# FMU_FMU_REV_2A.net
KiCad netlist of a schematic drawn in Altium Designer
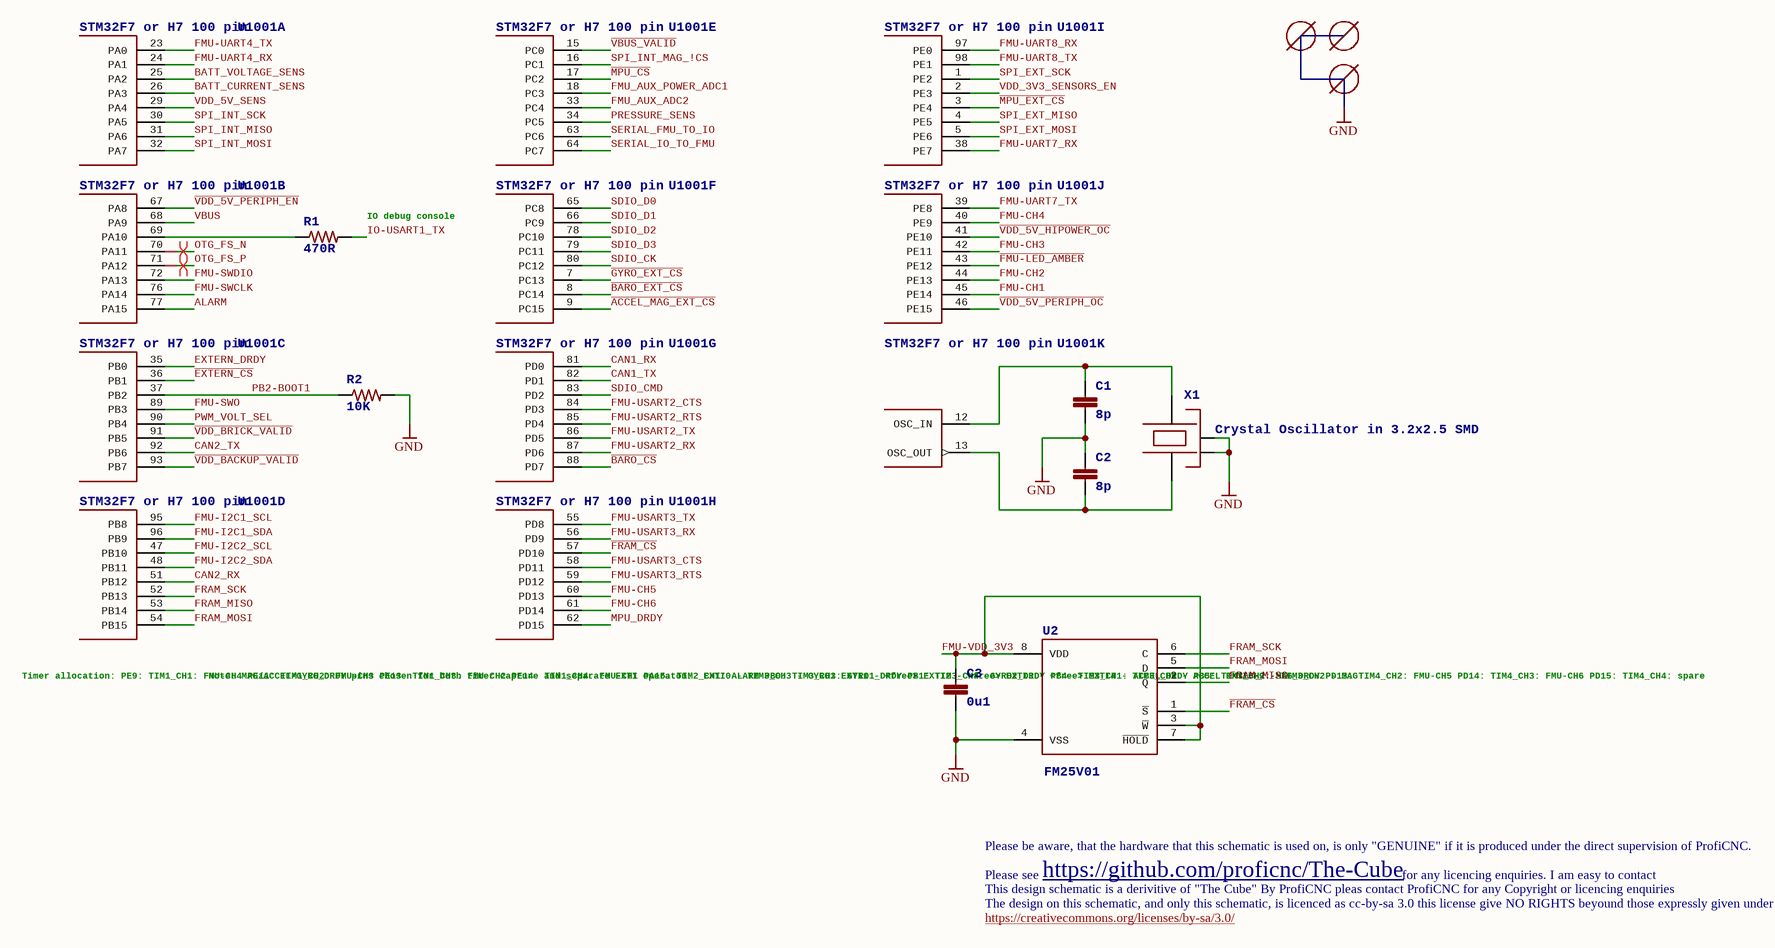
[diagram p0: FMU_FMU_REV_2A.SchDoc]

(export (version "E")
  (design (tool "Eeschema 10.0.6"))
  (components
    (comp (ref "C1")
      (value "8p")
      (footprint "0402-CAP")
      (description "CAP CER 8PF 50V C0G 0402")
      (libsource (lib "pixhawk2") (part "CAP0402"))
    )
    (comp (ref "C2")
      (value "8p")
      (footprint "0402-CAP")
      (description "CAP CER 8PF 50V C0G 0402")
      (libsource (lib "pixhawk2") (part "CAP0402"))
    )
    (comp (ref "C3")
      (value "0u1")
      (footprint "0402-CAP")
      (description "CAP CER 0.1UF 16V Y5V 0402")
      (libsource (lib "pixhawk2") (part "CAP0402"))
    )
    (comp (ref "M1")
      (value "MOUNT-HOLE1.8MM")
      (footprint "MOUNT-HOLE1.8")
      (libsource (lib "pixhawk2") (part "MOUNT-HOLE1.8MM"))
    )
    (comp (ref "M2")
      (value "MOUNT-HOLE1.8MM")
      (footprint "MOUNT-HOLE1.8")
      (libsource (lib "pixhawk2") (part "MOUNT-HOLE1.8MM"))
    )
    (comp (ref "M3")
      (value "MOUNT-HOLE1.8MM")
      (footprint "MOUNT-HOLE1.8")
      (libsource (lib "pixhawk2") (part "MOUNT-HOLE1.8MM"))
    )
    (comp (ref "R1")
      (value "470R")
      (footprint "0402-RES")
      (description "RES 470 OHM 1/16W 1% 0402 SMD")
      (libsource (lib "pixhawk2") (part "RESISTOR0402-RES"))
    )
    (comp (ref "R2")
      (value "10K")
      (footprint "0402-RES")
      (description "RES 10K OHM 1/16W 1% 0402 SMD")
      (libsource (lib "pixhawk2") (part "RESISTOR0402-RES"))
    )
    (comp (ref "U2")
      (value "FM25V01")
      (footprint "SO08")
      (description "IC FRAM 128KBIT 40MHZ 8SOIC")
      (libsource (lib "pixhawk2") (part "FM25V01"))
    )
    (comp (ref "U1001")
      (value "STM32F7 or H7 100 pin")
      (footprint "TQFP100")
      (description "REV 3 Silicon or later IC MCU ARM 2MB FLASH 100LQFP")
      (libsource (lib "pixhawk2") (part "STM32F4X7VX"))
    )
    (comp (ref "X1")
      (value "Crystal Oscillator in 3.2x2.5 SMD")
      (footprint "OSCILLATOR-3.2X2.5")
      (description "CRYSTAL 24MHZ 8PF SMD")
      (libsource (lib "pixhawk2") (part "OSCILLATOR-3.2X2.5"))
    )
  )
  (nets
    (net (code "1") (name "/ALARM") (class "Default")
      (node (ref "U1001") (pin "77") (pinfunction "PA15_77") (pintype "passive"))
    )
    (net (code "2") (name "/BATT_CURRENT_SENS") (class "Default")
      (node (ref "U1001") (pin "26") (pinfunction "PA3_26") (pintype "passive"))
    )
    (net (code "3") (name "/BATT_VOLTAGE_SENS") (class "Default")
      (node (ref "U1001") (pin "25") (pinfunction "PA2_25") (pintype "passive"))
    )
    (net (code "4") (name "/CAN1_RX") (class "Default")
      (node (ref "U1001") (pin "81") (pinfunction "PD0_81") (pintype "passive"))
    )
    (net (code "5") (name "/CAN1_TX") (class "Default")
      (node (ref "U1001") (pin "82") (pinfunction "PD1_82") (pintype "passive"))
    )
    (net (code "6") (name "/CAN2_RX") (class "Default")
      (node (ref "U1001") (pin "51") (pinfunction "PB12_51") (pintype "passive"))
    )
    (net (code "7") (name "/CAN2_TX") (class "Default")
      (node (ref "U1001") (pin "92") (pinfunction "PB6_92") (pintype "passive"))
    )
    (net (code "8") (name "/EXTERN_DRDY") (class "Default")
      (node (ref "U1001") (pin "35") (pinfunction "PB0_35") (pintype "passive"))
    )
    (net (code "9") (name "/FMU-CH1") (class "Default")
      (node (ref "U1001") (pin "45") (pinfunction "PE14_45") (pintype "passive"))
    )
    (net (code "10") (name "/FMU-CH2") (class "Default")
      (node (ref "U1001") (pin "44") (pinfunction "PE13_44") (pintype "passive"))
    )
    (net (code "11") (name "/FMU-CH3") (class "Default")
      (node (ref "U1001") (pin "42") (pinfunction "PE11_42") (pintype "passive"))
    )
    (net (code "12") (name "/FMU-CH4") (class "Default")
      (node (ref "U1001") (pin "40") (pinfunction "PE9_40") (pintype "passive"))
    )
    (net (code "13") (name "/FMU-CH5") (class "Default")
      (node (ref "U1001") (pin "60") (pinfunction "PD13_60") (pintype "passive"))
    )
    (net (code "14") (name "/FMU-CH6") (class "Default")
      (node (ref "U1001") (pin "61") (pinfunction "PD14_61") (pintype "passive"))
    )
    (net (code "15") (name "/FMU-I2C1_SCL") (class "Default")
      (node (ref "U1001") (pin "95") (pinfunction "PB8_95") (pintype "passive"))
    )
    (net (code "16") (name "/FMU-I2C1_SDA") (class "Default")
      (node (ref "U1001") (pin "96") (pinfunction "PB9_96") (pintype "passive"))
    )
    (net (code "17") (name "/FMU-I2C2_SCL") (class "Default")
      (node (ref "U1001") (pin "47") (pinfunction "PB10_47") (pintype "passive"))
    )
    (net (code "18") (name "/FMU-I2C2_SDA") (class "Default")
      (node (ref "U1001") (pin "48") (pinfunction "PB11_48") (pintype "passive"))
    )
    (net (code "19") (name "/FMU-SWCLK") (class "Default")
      (node (ref "U1001") (pin "76") (pinfunction "PA14_76") (pintype "passive"))
    )
    (net (code "20") (name "/FMU-SWDIO") (class "Default")
      (node (ref "U1001") (pin "72") (pinfunction "PA13_72") (pintype "passive"))
    )
    (net (code "21") (name "/FMU-SWO") (class "Default")
      (node (ref "U1001") (pin "89") (pinfunction "PB3_89") (pintype "passive"))
    )
    (net (code "22") (name "/FMU-UART4_RX") (class "Default")
      (node (ref "U1001") (pin "24") (pinfunction "PA1_24") (pintype "passive"))
    )
    (net (code "23") (name "/FMU-UART4_TX") (class "Default")
      (node (ref "U1001") (pin "23") (pinfunction "PA0_23") (pintype "passive"))
    )
    (net (code "24") (name "/FMU-UART7_RX") (class "Default")
      (node (ref "U1001") (pin "38") (pinfunction "PE7_38") (pintype "passive"))
    )
    (net (code "25") (name "/FMU-UART7_TX") (class "Default")
      (node (ref "U1001") (pin "39") (pinfunction "PE8_39") (pintype "passive"))
    )
    (net (code "26") (name "/FMU-UART8_RX") (class "Default")
      (node (ref "U1001") (pin "97") (pinfunction "PE0_97") (pintype "passive"))
    )
    (net (code "27") (name "/FMU-UART8_TX") (class "Default")
      (node (ref "U1001") (pin "98") (pinfunction "PE1_98") (pintype "passive"))
    )
    (net (code "28") (name "/FMU-USART2_CTS") (class "Default")
      (node (ref "U1001") (pin "84") (pinfunction "PD3_84") (pintype "passive"))
    )
    (net (code "29") (name "/FMU-USART2_RTS") (class "Default")
      (node (ref "U1001") (pin "85") (pinfunction "PD4_85") (pintype "passive"))
    )
    (net (code "30") (name "/FMU-USART2_RX") (class "Default")
      (node (ref "U1001") (pin "87") (pinfunction "PD6_87") (pintype "passive"))
    )
    (net (code "31") (name "/FMU-USART2_TX") (class "Default")
      (node (ref "U1001") (pin "86") (pinfunction "PD5_86") (pintype "passive"))
    )
    (net (code "32") (name "/FMU-USART3_CTS") (class "Default")
      (node (ref "U1001") (pin "58") (pinfunction "PD11_58") (pintype "passive"))
    )
    (net (code "33") (name "/FMU-USART3_RTS") (class "Default")
      (node (ref "U1001") (pin "59") (pinfunction "PD12_59") (pintype "passive"))
    )
    (net (code "34") (name "/FMU-USART3_RX") (class "Default")
      (node (ref "U1001") (pin "56") (pinfunction "PD9_56") (pintype "passive"))
    )
    (net (code "35") (name "/FMU-USART3_TX") (class "Default")
      (node (ref "U1001") (pin "55") (pinfunction "PD8_55") (pintype "passive"))
    )
    (net (code "36") (name "/FMU-VDD_3V3") (class "Default")
      (node (ref "C3") (pin "P$1") (pinfunction "1_P$1") (pintype "passive"))
      (node (ref "U2") (pin "3") (pinfunction "~{W}_3") (pintype "passive"))
      (node (ref "U2") (pin "7") (pinfunction "~{HOLD}_7") (pintype "passive"))
      (node (ref "U2") (pin "8") (pinfunction "VDD_8") (pintype "passive"))
    )
    (net (code "37") (name "/FMU_AUX_ADC2") (class "Default")
      (node (ref "U1001") (pin "33") (pinfunction "PC4_33") (pintype "passive"))
    )
    (net (code "38") (name "/FMU_AUX_POWER_ADC1") (class "Default")
      (node (ref "U1001") (pin "18") (pinfunction "PC3_18") (pintype "passive"))
    )
    (net (code "39") (name "/FRAM_MISO") (class "Default")
      (node (ref "U1001") (pin "53") (pinfunction "PB14_53") (pintype "passive"))
      (node (ref "U2") (pin "2") (pinfunction "Q_2") (pintype "passive"))
    )
    (net (code "40") (name "/FRAM_MOSI") (class "Default")
      (node (ref "U1001") (pin "54") (pinfunction "PB15_54") (pintype "passive"))
      (node (ref "U2") (pin "5") (pinfunction "D_5") (pintype "passive"))
    )
    (net (code "41") (name "/FRAM_SCK") (class "Default")
      (node (ref "U1001") (pin "52") (pinfunction "PB13_52") (pintype "passive"))
      (node (ref "U2") (pin "6") (pinfunction "C_6") (pintype "passive"))
    )
    (net (code "42") (name "/IO-USART1_TX") (class "Default")
      (node (ref "R1") (pin "P$2") (pinfunction "2_P$2") (pintype "passive"))
    )
    (net (code "43") (name "/MPU_DRDY") (class "Default")
      (node (ref "U1001") (pin "62") (pinfunction "PD15_62") (pintype "passive"))
    )
    (net (code "44") (name "/OTG_FS_N") (class "Default")
      (node (ref "U1001") (pin "70") (pinfunction "PA11_70") (pintype "passive"))
    )
    (net (code "45") (name "/OTG_FS_P") (class "Default")
      (node (ref "U1001") (pin "71") (pinfunction "PA12_71") (pintype "passive"))
    )
    (net (code "46") (name "/PB2-BOOT1") (class "Default")
      (node (ref "R2") (pin "P$1") (pinfunction "1_P$1") (pintype "passive"))
      (node (ref "U1001") (pin "37") (pinfunction "PB2_37") (pintype "passive"))
    )
    (net (code "47") (name "/PRESSURE_SENS") (class "Default")
      (node (ref "U1001") (pin "34") (pinfunction "PC5_34") (pintype "passive"))
    )
    (net (code "48") (name "/PWM_VOLT_SEL") (class "Default")
      (node (ref "U1001") (pin "90") (pinfunction "PB4_90") (pintype "passive"))
    )
    (net (code "49") (name "/SDIO_CK") (class "Default")
      (node (ref "U1001") (pin "80") (pinfunction "PC12_80") (pintype "passive"))
    )
    (net (code "50") (name "/SDIO_CMD") (class "Default")
      (node (ref "U1001") (pin "83") (pinfunction "PD2_83") (pintype "passive"))
    )
    (net (code "51") (name "/SDIO_D0") (class "Default")
      (node (ref "U1001") (pin "65") (pinfunction "PC8_65") (pintype "passive"))
    )
    (net (code "52") (name "/SDIO_D1") (class "Default")
      (node (ref "U1001") (pin "66") (pinfunction "PC9_66") (pintype "passive"))
    )
    (net (code "53") (name "/SDIO_D2") (class "Default")
      (node (ref "U1001") (pin "78") (pinfunction "PC10_78") (pintype "passive"))
    )
    (net (code "54") (name "/SDIO_D3") (class "Default")
      (node (ref "U1001") (pin "79") (pinfunction "PC11_79") (pintype "passive"))
    )
    (net (code "55") (name "/SERIAL_FMU_TO_IO") (class "Default")
      (node (ref "U1001") (pin "63") (pinfunction "PC6_63") (pintype "passive"))
    )
    (net (code "56") (name "/SERIAL_IO_TO_FMU") (class "Default")
      (node (ref "U1001") (pin "64") (pinfunction "PC7_64") (pintype "passive"))
    )
    (net (code "57") (name "/SPI_EXT_MISO") (class "Default")
      (node (ref "U1001") (pin "4") (pinfunction "PE5_4") (pintype "passive"))
    )
    (net (code "58") (name "/SPI_EXT_MOSI") (class "Default")
      (node (ref "U1001") (pin "5") (pinfunction "PE6_5") (pintype "passive"))
    )
    (net (code "59") (name "/SPI_EXT_SCK") (class "Default")
      (node (ref "U1001") (pin "1") (pinfunction "PE2_1") (pintype "passive"))
    )
    (net (code "60") (name "/SPI_INT_MAG_!CS") (class "Default")
      (node (ref "U1001") (pin "16") (pinfunction "PC1_16") (pintype "passive"))
    )
    (net (code "61") (name "/SPI_INT_MISO") (class "Default")
      (node (ref "U1001") (pin "31") (pinfunction "PA6_31") (pintype "passive"))
    )
    (net (code "62") (name "/SPI_INT_MOSI") (class "Default")
      (node (ref "U1001") (pin "32") (pinfunction "PA7_32") (pintype "passive"))
    )
    (net (code "63") (name "/SPI_INT_SCK") (class "Default")
      (node (ref "U1001") (pin "30") (pinfunction "PA5_30") (pintype "passive"))
    )
    (net (code "64") (name "/VBUS") (class "Default")
      (node (ref "U1001") (pin "68") (pinfunction "PA9_68") (pintype "passive"))
    )
    (net (code "65") (name "/VDD_3V3_SENSORS_EN") (class "Default")
      (node (ref "U1001") (pin "2") (pinfunction "PE3_2") (pintype "passive"))
    )
    (net (code "66") (name "/VDD_5V_SENS") (class "Default")
      (node (ref "U1001") (pin "29") (pinfunction "PA4_29") (pintype "passive"))
    )
    (net (code "67") (name "/~{ACCEL_MAG_EXT_CS}") (class "Default")
      (node (ref "U1001") (pin "9") (pinfunction "PC15_9") (pintype "passive"))
    )
    (net (code "68") (name "/~{BARO_CS}") (class "Default")
      (node (ref "U1001") (pin "88") (pinfunction "PD7_88") (pintype "passive"))
    )
    (net (code "69") (name "/~{BARO_EXT_CS}") (class "Default")
      (node (ref "U1001") (pin "8") (pinfunction "PC14_8") (pintype "passive"))
    )
    (net (code "70") (name "/~{EXTERN_CS}") (class "Default")
      (node (ref "U1001") (pin "36") (pinfunction "PB1_36") (pintype "passive"))
    )
    (net (code "71") (name "/~{FMU-LED_AMBER}") (class "Default")
      (node (ref "U1001") (pin "43") (pinfunction "PE12_43") (pintype "passive"))
    )
    (net (code "72") (name "/~{FRAM_CS}") (class "Default")
      (node (ref "U1001") (pin "57") (pinfunction "PD10_57") (pintype "passive"))
      (node (ref "U2") (pin "1") (pinfunction "~{S}_1") (pintype "passive"))
    )
    (net (code "73") (name "/~{GYRO_EXT_CS}") (class "Default")
      (node (ref "U1001") (pin "7") (pinfunction "PC13_7") (pintype "passive"))
    )
    (net (code "74") (name "/~{MPU_CS}") (class "Default")
      (node (ref "U1001") (pin "17") (pinfunction "PC2_17") (pintype "passive"))
    )
    (net (code "75") (name "/~{MPU_EXT_CS}") (class "Default")
      (node (ref "U1001") (pin "3") (pinfunction "PE4_3") (pintype "passive"))
    )
    (net (code "76") (name "/~{VBUS_VALID}") (class "Default")
      (node (ref "U1001") (pin "15") (pinfunction "PC0_15") (pintype "passive"))
    )
    (net (code "77") (name "/~{VDD_5V_HIPOWER_OC}") (class "Default")
      (node (ref "U1001") (pin "41") (pinfunction "PE10_41") (pintype "passive"))
    )
    (net (code "78") (name "/~{VDD_5V_PERIPH_EN}") (class "Default")
      (node (ref "U1001") (pin "67") (pinfunction "PA8_67") (pintype "passive"))
    )
    (net (code "79") (name "/~{VDD_5V_PERIPH_OC}") (class "Default")
      (node (ref "U1001") (pin "46") (pinfunction "PE15_46") (pintype "passive"))
    )
    (net (code "80") (name "/~{VDD_BACKUP_VALID}") (class "Default")
      (node (ref "U1001") (pin "93") (pinfunction "PB7_93") (pintype "passive"))
    )
    (net (code "81") (name "/~{VDD_BRICK_VALID}") (class "Default")
      (node (ref "U1001") (pin "91") (pinfunction "PB5_91") (pintype "passive"))
    )
    (net (code "82") (name "GND") (class "Default")
      (node (ref "C1") (pin "P$2") (pinfunction "2_P$2") (pintype "passive"))
      (node (ref "C2") (pin "P$1") (pinfunction "1_P$1") (pintype "passive"))
      (node (ref "C3") (pin "P$2") (pinfunction "2_P$2") (pintype "passive"))
      (node (ref "R2") (pin "P$2") (pinfunction "2_P$2") (pintype "passive"))
      (node (ref "U2") (pin "4") (pinfunction "VSS_4") (pintype "passive"))
      (node (ref "X1") (pin "2") (pinfunction "NC_2_2") (pintype "open_emitter"))
      (node (ref "X1") (pin "4") (pinfunction "NC_4_4") (pintype "open_emitter"))
    )
    (net (code "83") (name "Net-(C1-1)") (class "Default")
      (node (ref "C1") (pin "P$1") (pinfunction "1_P$1") (pintype "passive"))
      (node (ref "U1001") (pin "12") (pinfunction "OSC_IN_12") (pintype "passive"))
      (node (ref "X1") (pin "3") (pinfunction "3_3") (pintype "passive"))
    )
    (net (code "84") (name "Net-(C2-2)") (class "Default")
      (node (ref "C2") (pin "P$2") (pinfunction "2_P$2") (pintype "passive"))
      (node (ref "U1001") (pin "13") (pinfunction "OSC_OUT_13") (pintype "output"))
      (node (ref "X1") (pin "1") (pinfunction "1_1") (pintype "passive"))
    )
    (net (code "85") (name "Net-(R1-1)") (class "Default")
      (node (ref "R1") (pin "P$1") (pinfunction "1_P$1") (pintype "passive"))
      (node (ref "U1001") (pin "69") (pinfunction "PA10_69") (pintype "passive"))
    )
  )
)
